# mixer-board4.net
KiCad netlist of a schematic drawn in EAGLE
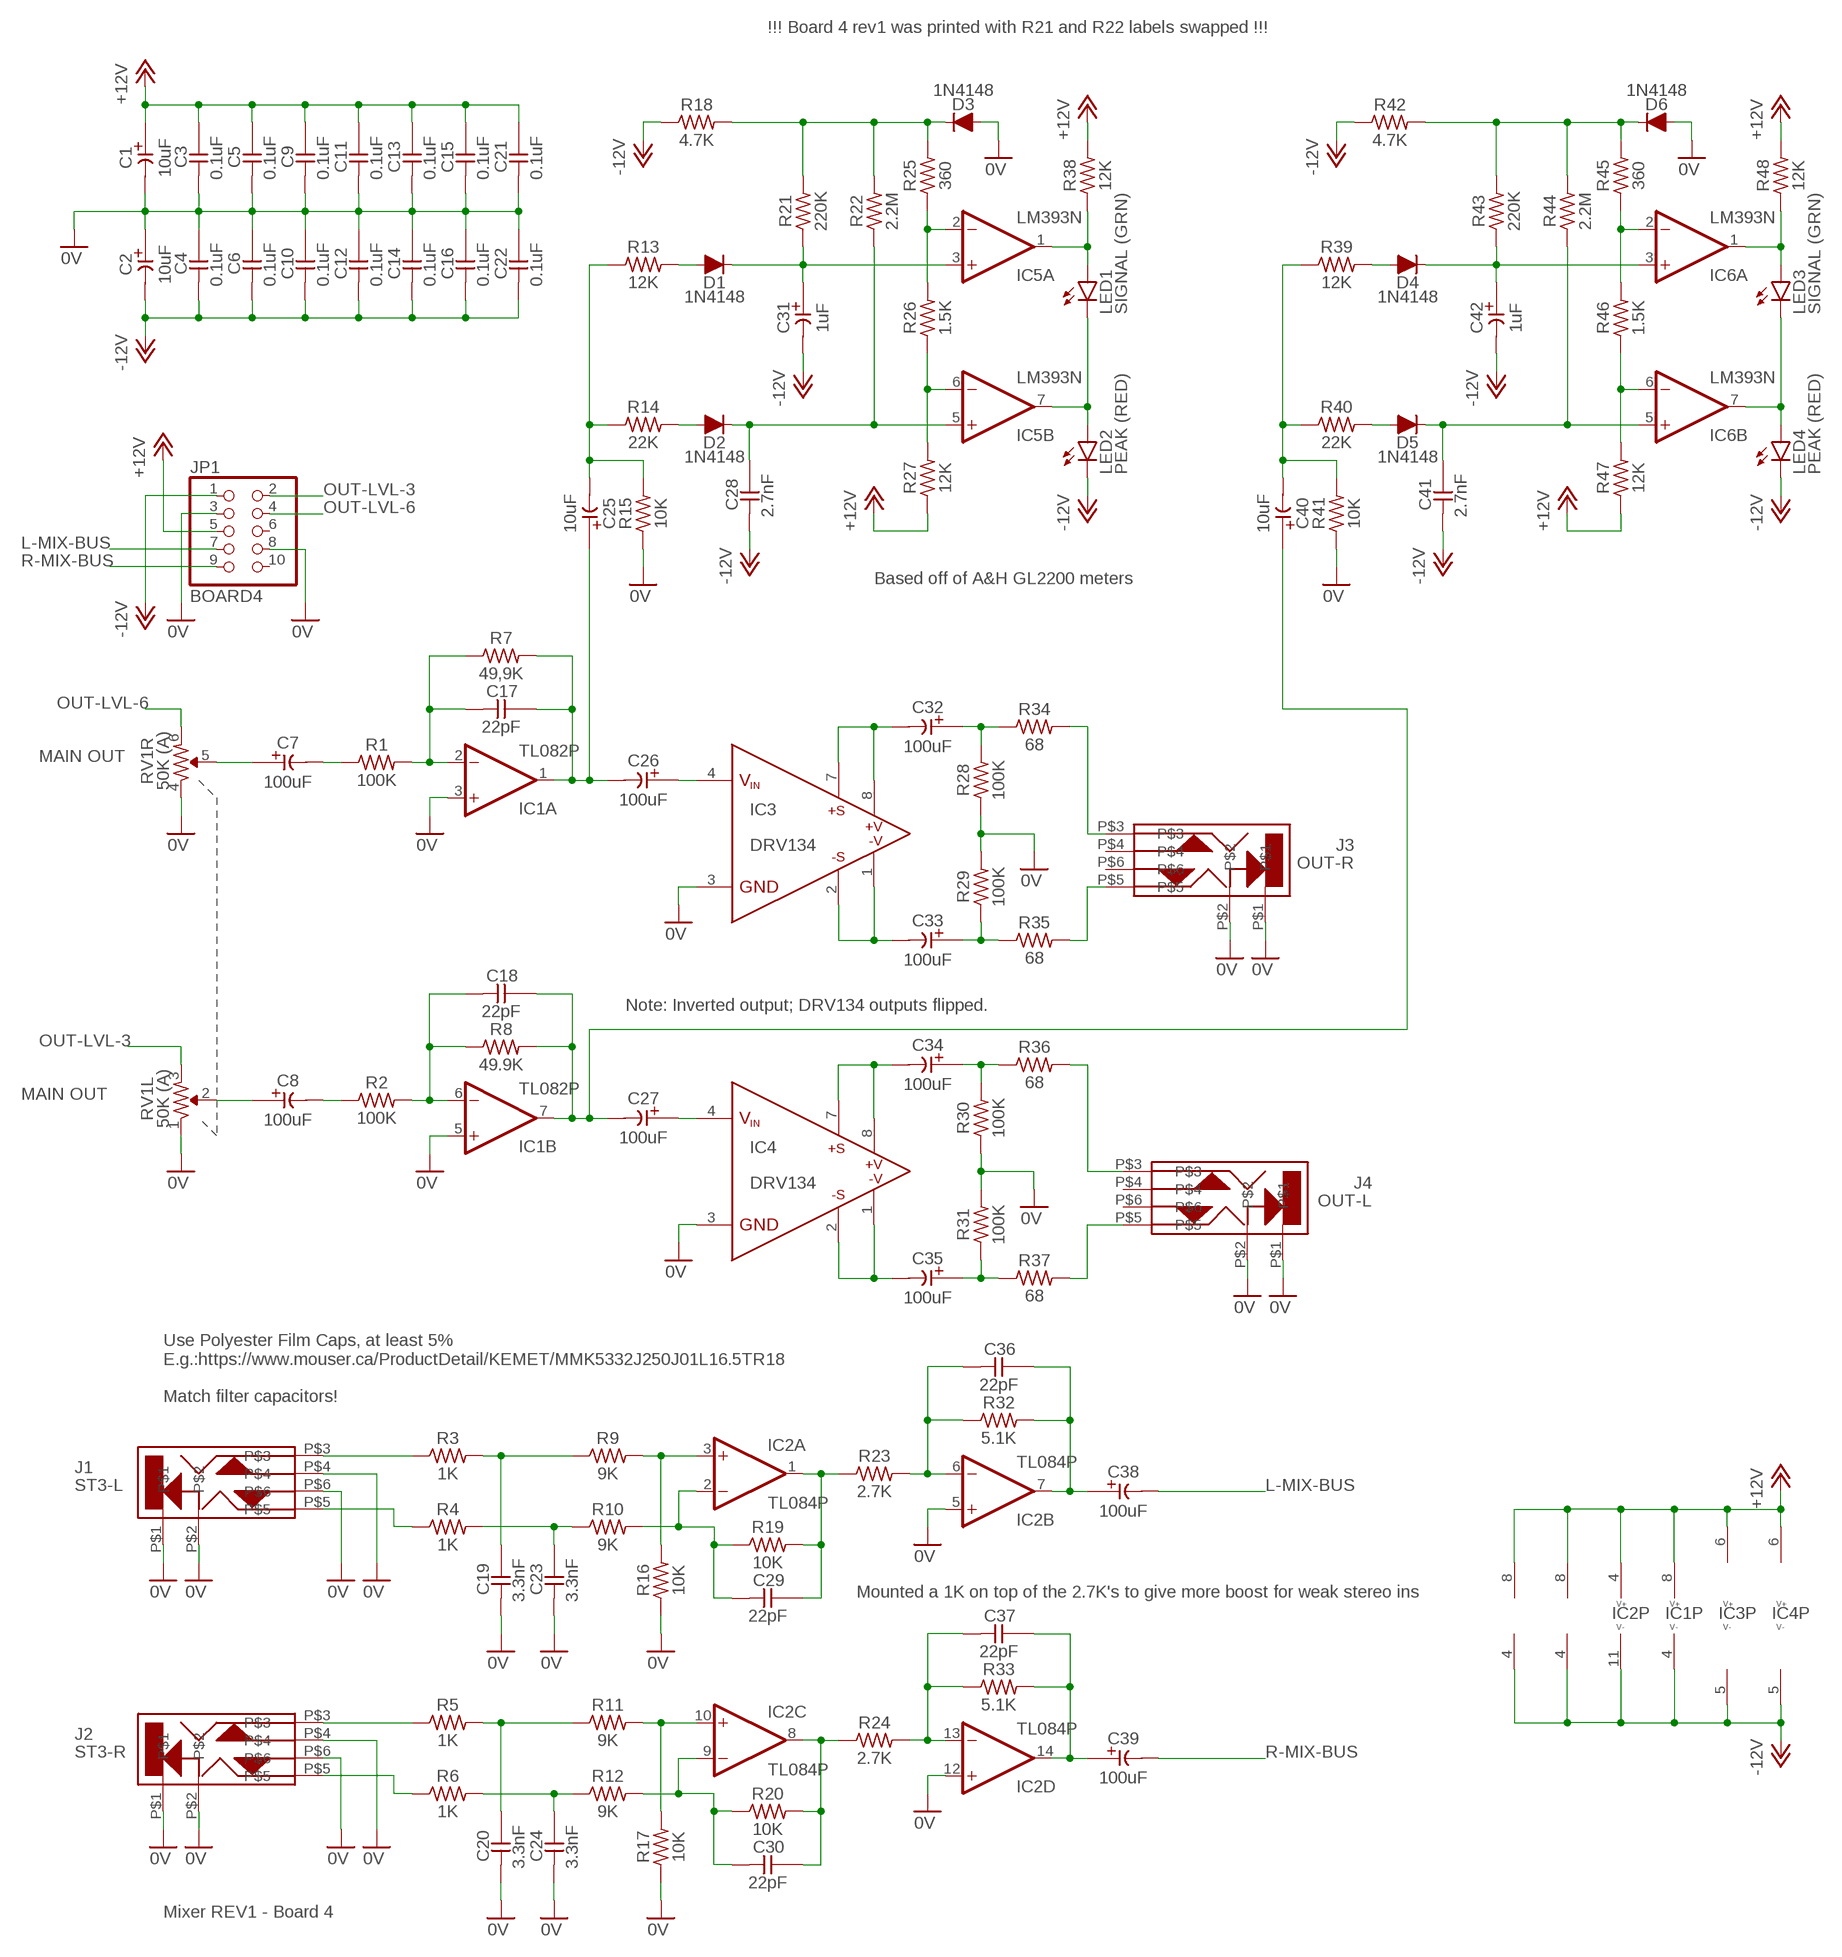
[diagram p0: schematic, sheet 1]

(export (version "E")
  (design (tool "Eeschema 10.0.6"))
  (components
    (comp (ref "C1")
      (value "10uF")
      (footprint "eagle-import:E2-5")
      (libsource (lib "eagle-import") (part "CE-USE2-5"))
    )
    (comp (ref "C2")
      (value "10uF")
      (footprint "eagle-import:E2-5")
      (libsource (lib "eagle-import") (part "CE-USE2-5"))
    )
    (comp (ref "C3")
      (value "0.1uF")
      (footprint "eagle-import:C025-024X044")
      (libsource (lib "eagle-import") (part "CC-US025-024X044"))
    )
    (comp (ref "C4")
      (value "0.1uF")
      (footprint "eagle-import:C025-024X044")
      (libsource (lib "eagle-import") (part "CC-US025-024X044"))
    )
    (comp (ref "C5")
      (value "0.1uF")
      (footprint "eagle-import:C025-024X044")
      (libsource (lib "eagle-import") (part "CC-US025-024X044"))
    )
    (comp (ref "C6")
      (value "0.1uF")
      (footprint "eagle-import:C025-024X044")
      (libsource (lib "eagle-import") (part "CC-US025-024X044"))
    )
    (comp (ref "C7")
      (value "100uF")
      (footprint "eagle-import:E5-8,5")
      (libsource (lib "eagle-import") (part "CE-USE5-8.5"))
    )
    (comp (ref "C8")
      (value "100uF")
      (footprint "eagle-import:E5-8,5")
      (libsource (lib "eagle-import") (part "CE-USE5-8.5"))
    )
    (comp (ref "C9")
      (value "0.1uF")
      (footprint "eagle-import:C025-024X044")
      (libsource (lib "eagle-import") (part "CC-US025-024X044"))
    )
    (comp (ref "C10")
      (value "0.1uF")
      (footprint "eagle-import:C025-024X044")
      (libsource (lib "eagle-import") (part "CC-US025-024X044"))
    )
    (comp (ref "C11")
      (value "0.1uF")
      (footprint "eagle-import:C025-024X044")
      (libsource (lib "eagle-import") (part "CC-US025-024X044"))
    )
    (comp (ref "C12")
      (value "0.1uF")
      (footprint "eagle-import:C025-024X044")
      (libsource (lib "eagle-import") (part "CC-US025-024X044"))
    )
    (comp (ref "C13")
      (value "0.1uF")
      (footprint "eagle-import:C025-024X044")
      (libsource (lib "eagle-import") (part "CC-US025-024X044"))
    )
    (comp (ref "C14")
      (value "0.1uF")
      (footprint "eagle-import:C025-024X044")
      (libsource (lib "eagle-import") (part "CC-US025-024X044"))
    )
    (comp (ref "C15")
      (value "0.1uF")
      (footprint "eagle-import:C025-024X044")
      (libsource (lib "eagle-import") (part "CC-US025-024X044"))
    )
    (comp (ref "C16")
      (value "0.1uF")
      (footprint "eagle-import:C025-024X044")
      (libsource (lib "eagle-import") (part "CC-US025-024X044"))
    )
    (comp (ref "C17")
      (value "22pF")
      (footprint "eagle-import:C025-024X044")
      (libsource (lib "eagle-import") (part "CC-US025-024X044"))
    )
    (comp (ref "C18")
      (value "22pF")
      (footprint "eagle-import:C025-024X044")
      (libsource (lib "eagle-import") (part "CC-US025-024X044"))
    )
    (comp (ref "C19")
      (value "3.3nF")
      (footprint "eagle-import:C050-024X044")
      (libsource (lib "eagle-import") (part "CC-US050-024X044"))
    )
    (comp (ref "C20")
      (value "3.3nF")
      (footprint "eagle-import:C050-024X044")
      (libsource (lib "eagle-import") (part "CC-US050-024X044"))
    )
    (comp (ref "C21")
      (value "0.1uF")
      (footprint "eagle-import:C025-024X044")
      (libsource (lib "eagle-import") (part "CC-US025-024X044"))
    )
    (comp (ref "C22")
      (value "0.1uF")
      (footprint "eagle-import:C025-024X044")
      (libsource (lib "eagle-import") (part "CC-US025-024X044"))
    )
    (comp (ref "C23")
      (value "3.3nF")
      (footprint "eagle-import:C050-024X044")
      (libsource (lib "eagle-import") (part "CC-US050-024X044"))
    )
    (comp (ref "C24")
      (value "3.3nF")
      (footprint "eagle-import:C050-024X044")
      (libsource (lib "eagle-import") (part "CC-US050-024X044"))
    )
    (comp (ref "C25")
      (value "10uF")
      (footprint "eagle-import:E2-5")
      (libsource (lib "eagle-import") (part "CE-USE2-5"))
    )
    (comp (ref "C26")
      (value "100uF")
      (footprint "eagle-import:E5-8,5")
      (libsource (lib "eagle-import") (part "CE-USE5-8.5"))
    )
    (comp (ref "C27")
      (value "100uF")
      (footprint "eagle-import:E5-8,5")
      (libsource (lib "eagle-import") (part "CE-USE5-8.5"))
    )
    (comp (ref "C28")
      (value "2.7nF")
      (footprint "eagle-import:C025-024X044")
      (libsource (lib "eagle-import") (part "CC-US025-024X044"))
    )
    (comp (ref "C29")
      (value "22pF")
      (footprint "eagle-import:C025-024X044")
      (libsource (lib "eagle-import") (part "CC-US025-024X044"))
    )
    (comp (ref "C30")
      (value "22pF")
      (footprint "eagle-import:C025-024X044")
      (libsource (lib "eagle-import") (part "CC-US025-024X044"))
    )
    (comp (ref "C31")
      (value "1uF")
      (footprint "eagle-import:E2-5")
      (libsource (lib "eagle-import") (part "CE-USE2-5"))
    )
    (comp (ref "C32")
      (value "100uF")
      (footprint "eagle-import:E5-8,5")
      (libsource (lib "eagle-import") (part "CE-USE5-8.5"))
    )
    (comp (ref "C33")
      (value "100uF")
      (footprint "eagle-import:E5-8,5")
      (libsource (lib "eagle-import") (part "CE-USE5-8.5"))
    )
    (comp (ref "C34")
      (value "100uF")
      (footprint "eagle-import:E5-8,5")
      (libsource (lib "eagle-import") (part "CE-USE5-8.5"))
    )
    (comp (ref "C35")
      (value "100uF")
      (footprint "eagle-import:E5-8,5")
      (libsource (lib "eagle-import") (part "CE-USE5-8.5"))
    )
    (comp (ref "C36")
      (value "22pF")
      (footprint "eagle-import:C025-024X044")
      (libsource (lib "eagle-import") (part "CC-US025-024X044"))
    )
    (comp (ref "C37")
      (value "22pF")
      (footprint "eagle-import:C025-024X044")
      (libsource (lib "eagle-import") (part "CC-US025-024X044"))
    )
    (comp (ref "C38")
      (value "100uF")
      (footprint "eagle-import:E5-8,5")
      (libsource (lib "eagle-import") (part "CE-USE5-8.5"))
    )
    (comp (ref "C39")
      (value "100uF")
      (footprint "eagle-import:E5-8,5")
      (libsource (lib "eagle-import") (part "CE-USE5-8.5"))
    )
    (comp (ref "C40")
      (value "10uF")
      (footprint "eagle-import:E2-5")
      (libsource (lib "eagle-import") (part "CE-USE2-5"))
    )
    (comp (ref "C41")
      (value "2.7nF")
      (footprint "eagle-import:C025-024X044")
      (libsource (lib "eagle-import") (part "CC-US025-024X044"))
    )
    (comp (ref "C42")
      (value "1uF")
      (footprint "eagle-import:E2-5")
      (libsource (lib "eagle-import") (part "CE-USE2-5"))
    )
    (comp (ref "D1")
      (value "1N4148")
      (footprint "eagle-import:DO34-5")
      (libsource (lib "eagle-import") (part "1N4148"))
    )
    (comp (ref "D2")
      (value "1N4148")
      (footprint "eagle-import:DO34-5")
      (libsource (lib "eagle-import") (part "1N4148"))
    )
    (comp (ref "D3")
      (value "1N4148")
      (footprint "eagle-import:DO34-5")
      (libsource (lib "eagle-import") (part "1N4148"))
    )
    (comp (ref "D4")
      (value "1N4148")
      (footprint "eagle-import:DO34-5")
      (libsource (lib "eagle-import") (part "1N4148"))
    )
    (comp (ref "D5")
      (value "1N4148")
      (footprint "eagle-import:DO34-5")
      (libsource (lib "eagle-import") (part "1N4148"))
    )
    (comp (ref "D6")
      (value "1N4148")
      (footprint "eagle-import:DO34-5")
      (libsource (lib "eagle-import") (part "1N4148"))
    )
    (comp (ref "IC1")
      (value "TL082P")
      (footprint "eagle-import:DIL08")
      (libsource (lib "eagle-import") (part "TL082P"))
    )
    (comp (ref "IC2")
      (value "TL084P")
      (footprint "eagle-import:DIL14")
      (libsource (lib "eagle-import") (part "TL084P"))
    )
    (comp (ref "IC3")
      (value "DRV134")
      (footprint "eagle-import:DIL08")
      (libsource (lib "eagle-import") (part "DRV134"))
    )
    (comp (ref "IC4")
      (value "DRV134")
      (footprint "eagle-import:DIL08")
      (libsource (lib "eagle-import") (part "DRV134"))
    )
    (comp (ref "IC5")
      (value "LM393N")
      (footprint "eagle-import:DIL08")
      (libsource (lib "eagle-import") (part "LM393N"))
    )
    (comp (ref "IC6")
      (value "LM393N")
      (footprint "eagle-import:DIL08")
      (libsource (lib "eagle-import") (part "LM393N"))
    )
    (comp (ref "J1")
      (value "ST3-L")
      (footprint "eagle-import:NYS216-U")
      (libsource (lib "eagle-import") (part "NYS216-U"))
    )
    (comp (ref "J2")
      (value "ST3-R")
      (footprint "eagle-import:NYS216-U")
      (libsource (lib "eagle-import") (part "NYS216-U"))
    )
    (comp (ref "J3")
      (value "OUT-R")
      (footprint "eagle-import:NYS216-U")
      (libsource (lib "eagle-import") (part "NYS216-U"))
    )
    (comp (ref "J4")
      (value "OUT-L")
      (footprint "eagle-import:NYS216-U")
      (libsource (lib "eagle-import") (part "NYS216-U"))
    )
    (comp (ref "JP1")
      (value "BOARD4")
      (footprint "eagle-import:2X05")
      (libsource (lib "eagle-import") (part "PINHD-2X5"))
    )
    (comp (ref "LED1")
      (value "SIGNAL (GRN)")
      (footprint "eagle-import:LED3MM")
      (libsource (lib "eagle-import") (part "LED3MM"))
    )
    (comp (ref "LED2")
      (value "PEAK (RED)")
      (footprint "eagle-import:LED3MM")
      (libsource (lib "eagle-import") (part "LED3MM"))
    )
    (comp (ref "LED3")
      (value "SIGNAL (GRN)")
      (footprint "eagle-import:LED3MM")
      (libsource (lib "eagle-import") (part "LED3MM"))
    )
    (comp (ref "LED4")
      (value "PEAK (RED)")
      (footprint "eagle-import:LED3MM")
      (libsource (lib "eagle-import") (part "LED3MM"))
    )
    (comp (ref "R1")
      (value "100K")
      (footprint "eagle-import:0207_7")
      (libsource (lib "eagle-import") (part "R"))
    )
    (comp (ref "R2")
      (value "100K")
      (footprint "eagle-import:0207_7")
      (libsource (lib "eagle-import") (part "R"))
    )
    (comp (ref "R3")
      (value "1K")
      (footprint "eagle-import:0207_7")
      (libsource (lib "eagle-import") (part "R"))
    )
    (comp (ref "R4")
      (value "1K")
      (footprint "eagle-import:0207_7")
      (libsource (lib "eagle-import") (part "R"))
    )
    (comp (ref "R5")
      (value "1K")
      (footprint "eagle-import:0207_7")
      (libsource (lib "eagle-import") (part "R"))
    )
    (comp (ref "R6")
      (value "1K")
      (footprint "eagle-import:0207_7")
      (libsource (lib "eagle-import") (part "R"))
    )
    (comp (ref "R7")
      (value "49,9K")
      (footprint "eagle-import:0207_7")
      (libsource (lib "eagle-import") (part "R"))
    )
    (comp (ref "R8")
      (value "49.9K")
      (footprint "eagle-import:0207_7")
      (libsource (lib "eagle-import") (part "R"))
    )
    (comp (ref "R9")
      (value "9K")
      (footprint "eagle-import:0207_7")
      (libsource (lib "eagle-import") (part "R"))
    )
    (comp (ref "R10")
      (value "9K")
      (footprint "eagle-import:0207_7")
      (libsource (lib "eagle-import") (part "R"))
    )
    (comp (ref "R11")
      (value "9K")
      (footprint "eagle-import:0207_7")
      (libsource (lib "eagle-import") (part "R"))
    )
    (comp (ref "R12")
      (value "9K")
      (footprint "eagle-import:0207_7")
      (libsource (lib "eagle-import") (part "R"))
    )
    (comp (ref "R13")
      (value "12K")
      (footprint "eagle-import:0207_7")
      (libsource (lib "eagle-import") (part "R"))
    )
    (comp (ref "R14")
      (value "22K")
      (footprint "eagle-import:0207_7")
      (libsource (lib "eagle-import") (part "R"))
    )
    (comp (ref "R15")
      (value "10K")
      (footprint "eagle-import:0207_7")
      (libsource (lib "eagle-import") (part "R"))
    )
    (comp (ref "R16")
      (value "10K")
      (footprint "eagle-import:0207_7")
      (libsource (lib "eagle-import") (part "R"))
    )
    (comp (ref "R17")
      (value "10K")
      (footprint "eagle-import:0207_7")
      (libsource (lib "eagle-import") (part "R"))
    )
    (comp (ref "R18")
      (value "4.7K")
      (footprint "eagle-import:0207_7")
      (libsource (lib "eagle-import") (part "R"))
    )
    (comp (ref "R19")
      (value "10K")
      (footprint "eagle-import:0207_7")
      (libsource (lib "eagle-import") (part "R"))
    )
    (comp (ref "R20")
      (value "10K")
      (footprint "eagle-import:0207_7")
      (libsource (lib "eagle-import") (part "R"))
    )
    (comp (ref "R21")
      (value "220K")
      (footprint "eagle-import:0207_7")
      (libsource (lib "eagle-import") (part "R"))
    )
    (comp (ref "R22")
      (value "2.2M")
      (footprint "eagle-import:0207_7")
      (libsource (lib "eagle-import") (part "R"))
    )
    (comp (ref "R23")
      (value "2.7K")
      (footprint "eagle-import:0207_7")
      (libsource (lib "eagle-import") (part "R"))
    )
    (comp (ref "R24")
      (value "2.7K")
      (footprint "eagle-import:0207_7")
      (libsource (lib "eagle-import") (part "R"))
    )
    (comp (ref "R25")
      (value "360")
      (footprint "eagle-import:0207_7")
      (libsource (lib "eagle-import") (part "R"))
    )
    (comp (ref "R26")
      (value "1.5K")
      (footprint "eagle-import:0207_7")
      (libsource (lib "eagle-import") (part "R"))
    )
    (comp (ref "R27")
      (value "12K")
      (footprint "eagle-import:0207_7")
      (libsource (lib "eagle-import") (part "R"))
    )
    (comp (ref "R28")
      (value "100K")
      (footprint "eagle-import:0207_7")
      (libsource (lib "eagle-import") (part "R"))
    )
    (comp (ref "R29")
      (value "100K")
      (footprint "eagle-import:0207_7")
      (libsource (lib "eagle-import") (part "R"))
    )
    (comp (ref "R30")
      (value "100K")
      (footprint "eagle-import:0207_7")
      (libsource (lib "eagle-import") (part "R"))
    )
    (comp (ref "R31")
      (value "100K")
      (footprint "eagle-import:0207_7")
      (libsource (lib "eagle-import") (part "R"))
    )
    (comp (ref "R32")
      (value "5.1K")
      (footprint "eagle-import:0207_7")
      (libsource (lib "eagle-import") (part "R"))
    )
    (comp (ref "R33")
      (value "5.1K")
      (footprint "eagle-import:0207_7")
      (libsource (lib "eagle-import") (part "R"))
    )
    (comp (ref "R34")
      (value "68")
      (footprint "eagle-import:0207_7")
      (libsource (lib "eagle-import") (part "R"))
    )
    (comp (ref "R35")
      (value "68")
      (footprint "eagle-import:0207_7")
      (libsource (lib "eagle-import") (part "R"))
    )
    (comp (ref "R36")
      (value "68")
      (footprint "eagle-import:0207_7")
      (libsource (lib "eagle-import") (part "R"))
    )
    (comp (ref "R37")
      (value "68")
      (footprint "eagle-import:0207_7")
      (libsource (lib "eagle-import") (part "R"))
    )
    (comp (ref "R38")
      (value "12K")
      (footprint "eagle-import:0207_7")
      (libsource (lib "eagle-import") (part "R"))
    )
    (comp (ref "R39")
      (value "12K")
      (footprint "eagle-import:0207_7")
      (libsource (lib "eagle-import") (part "R"))
    )
    (comp (ref "R40")
      (value "22K")
      (footprint "eagle-import:0207_7")
      (libsource (lib "eagle-import") (part "R"))
    )
    (comp (ref "R41")
      (value "10K")
      (footprint "eagle-import:0207_7")
      (libsource (lib "eagle-import") (part "R"))
    )
    (comp (ref "R42")
      (value "4.7K")
      (footprint "eagle-import:0207_7")
      (libsource (lib "eagle-import") (part "R"))
    )
    (comp (ref "R43")
      (value "220K")
      (footprint "eagle-import:0207_7")
      (libsource (lib "eagle-import") (part "R"))
    )
    (comp (ref "R44")
      (value "2.2M")
      (footprint "eagle-import:0207_7")
      (libsource (lib "eagle-import") (part "R"))
    )
    (comp (ref "R45")
      (value "360")
      (footprint "eagle-import:0207_7")
      (libsource (lib "eagle-import") (part "R"))
    )
    (comp (ref "R46")
      (value "1.5K")
      (footprint "eagle-import:0207_7")
      (libsource (lib "eagle-import") (part "R"))
    )
    (comp (ref "R47")
      (value "12K")
      (footprint "eagle-import:0207_7")
      (libsource (lib "eagle-import") (part "R"))
    )
    (comp (ref "R48")
      (value "12K")
      (footprint "eagle-import:0207_7")
      (libsource (lib "eagle-import") (part "R"))
    )
    (comp (ref "RV1")
      (value "50K (A)")
      (footprint "eagle-import:_COMMON_3RP_1610G")
      (libsource (lib "eagle-import") (part "R-VAR-ST"))
    )
  )
  (nets
    (net (code "1") (name "+12V") (class "Default")
      (node (ref "C1") (pin "+") (pinfunction "+_+") (pintype "passive"))
      (node (ref "C11") (pin "1") (pinfunction "1_1") (pintype "passive"))
      (node (ref "C13") (pin "1") (pinfunction "1_1") (pintype "passive"))
      (node (ref "C15") (pin "1") (pinfunction "1_1") (pintype "passive"))
      (node (ref "C21") (pin "1") (pinfunction "1_1") (pintype "passive"))
      (node (ref "C3") (pin "1") (pinfunction "1_1") (pintype "passive"))
      (node (ref "C5") (pin "1") (pinfunction "1_1") (pintype "passive"))
      (node (ref "C9") (pin "1") (pinfunction "1_1") (pintype "passive"))
      (node (ref "IC1") (pin "8") (pinfunction "V+_8") (pintype "power_in"))
      (node (ref "IC2") (pin "4") (pinfunction "V+_4") (pintype "power_in"))
      (node (ref "IC3") (pin "6") (pinfunction "V+_6") (pintype "power_in"))
      (node (ref "IC4") (pin "6") (pinfunction "V+_6") (pintype "power_in"))
      (node (ref "IC5") (pin "8") (pinfunction "V+_8") (pintype "power_in"))
      (node (ref "IC6") (pin "8") (pinfunction "V+_8") (pintype "power_in"))
      (node (ref "JP1") (pin "5") (pinfunction "5_5") (pintype "passive"))
      (node (ref "R27") (pin "1") (pinfunction "1_1") (pintype "passive"))
      (node (ref "R38") (pin "2") (pinfunction "2_2") (pintype "passive"))
      (node (ref "R47") (pin "1") (pinfunction "1_1") (pintype "passive"))
      (node (ref "R48") (pin "2") (pinfunction "2_2") (pintype "passive"))
    )
    (net (code "2") (name "-12V") (class "Default")
      (node (ref "C10") (pin "2") (pinfunction "2_2") (pintype "passive"))
      (node (ref "C12") (pin "2") (pinfunction "2_2") (pintype "passive"))
      (node (ref "C14") (pin "2") (pinfunction "2_2") (pintype "passive"))
      (node (ref "C16") (pin "2") (pinfunction "2_2") (pintype "passive"))
      (node (ref "C2") (pin "-") (pinfunction "-_-") (pintype "passive"))
      (node (ref "C22") (pin "2") (pinfunction "2_2") (pintype "passive"))
      (node (ref "C28") (pin "2") (pinfunction "2_2") (pintype "passive"))
      (node (ref "C31") (pin "-") (pinfunction "-_-") (pintype "passive"))
      (node (ref "C4") (pin "2") (pinfunction "2_2") (pintype "passive"))
      (node (ref "C41") (pin "2") (pinfunction "2_2") (pintype "passive"))
      (node (ref "C42") (pin "-") (pinfunction "-_-") (pintype "passive"))
      (node (ref "C6") (pin "2") (pinfunction "2_2") (pintype "passive"))
      (node (ref "IC1") (pin "4") (pinfunction "V-_4") (pintype "power_in"))
      (node (ref "IC2") (pin "11") (pinfunction "V-_11") (pintype "power_in"))
      (node (ref "IC3") (pin "5") (pinfunction "V-_5") (pintype "power_in"))
      (node (ref "IC4") (pin "5") (pinfunction "V-_5") (pintype "power_in"))
      (node (ref "IC5") (pin "4") (pinfunction "V-_4") (pintype "power_in"))
      (node (ref "IC6") (pin "4") (pinfunction "V-_4") (pintype "power_in"))
      (node (ref "JP1") (pin "1") (pinfunction "1_1") (pintype "passive"))
      (node (ref "LED2") (pin "K") (pinfunction "C_K") (pintype "passive"))
      (node (ref "LED4") (pin "K") (pinfunction "C_K") (pintype "passive"))
      (node (ref "R18") (pin "1") (pinfunction "1_1") (pintype "passive"))
      (node (ref "R42") (pin "1") (pinfunction "1_1") (pintype "passive"))
    )
    (net (code "3") (name "/L-MIX-BUS") (class "Default")
      (node (ref "C38") (pin "-") (pinfunction "-_-") (pintype "passive"))
      (node (ref "JP1") (pin "7") (pinfunction "7_7") (pintype "passive"))
    )
    (net (code "4") (name "/OUT-LVL-3") (class "Default")
      (node (ref "JP1") (pin "2") (pinfunction "2_2") (pintype "passive"))
      (node (ref "RV1") (pin "3") (pinfunction "3_3") (pintype "passive"))
    )
    (net (code "5") (name "/OUT-LVL-6") (class "Default")
      (node (ref "JP1") (pin "4") (pinfunction "4_4") (pintype "passive"))
      (node (ref "RV1") (pin "6") (pinfunction "3_6") (pintype "passive"))
    )
    (net (code "6") (name "/R-MIX-BUS") (class "Default")
      (node (ref "C39") (pin "-") (pinfunction "-_-") (pintype "passive"))
      (node (ref "JP1") (pin "9") (pinfunction "9_9") (pintype "passive"))
    )
    (net (code "7") (name "0V") (class "Default")
      (node (ref "C1") (pin "-") (pinfunction "-_-") (pintype "passive"))
      (node (ref "C10") (pin "1") (pinfunction "1_1") (pintype "passive"))
      (node (ref "C11") (pin "2") (pinfunction "2_2") (pintype "passive"))
      (node (ref "C12") (pin "1") (pinfunction "1_1") (pintype "passive"))
      (node (ref "C13") (pin "2") (pinfunction "2_2") (pintype "passive"))
      (node (ref "C14") (pin "1") (pinfunction "1_1") (pintype "passive"))
      (node (ref "C15") (pin "2") (pinfunction "2_2") (pintype "passive"))
      (node (ref "C16") (pin "1") (pinfunction "1_1") (pintype "passive"))
      (node (ref "C19") (pin "2") (pinfunction "2_2") (pintype "passive"))
      (node (ref "C2") (pin "+") (pinfunction "+_+") (pintype "passive"))
      (node (ref "C20") (pin "2") (pinfunction "2_2") (pintype "passive"))
      (node (ref "C21") (pin "2") (pinfunction "2_2") (pintype "passive"))
      (node (ref "C22") (pin "1") (pinfunction "1_1") (pintype "passive"))
      (node (ref "C23") (pin "2") (pinfunction "2_2") (pintype "passive"))
      (node (ref "C24") (pin "2") (pinfunction "2_2") (pintype "passive"))
      (node (ref "C3") (pin "2") (pinfunction "2_2") (pintype "passive"))
      (node (ref "C4") (pin "1") (pinfunction "1_1") (pintype "passive"))
      (node (ref "C5") (pin "2") (pinfunction "2_2") (pintype "passive"))
      (node (ref "C6") (pin "1") (pinfunction "1_1") (pintype "passive"))
      (node (ref "C9") (pin "2") (pinfunction "2_2") (pintype "passive"))
      (node (ref "D3") (pin "A") (pinfunction "A_A") (pintype "passive"))
      (node (ref "D6") (pin "A") (pinfunction "A_A") (pintype "passive"))
      (node (ref "IC1") (pin "3") (pinfunction "+IN_3") (pintype "input"))
      (node (ref "IC1") (pin "5") (pinfunction "+IN_5") (pintype "input"))
      (node (ref "IC2") (pin "12") (pinfunction "+IN_12") (pintype "input"))
      (node (ref "IC2") (pin "5") (pinfunction "+IN_5") (pintype "input"))
      (node (ref "IC3") (pin "3") (pinfunction "GND_3") (pintype "bidirectional"))
      (node (ref "IC4") (pin "3") (pinfunction "GND_3") (pintype "bidirectional"))
      (node (ref "J1") (pin "P$1") (pinfunction "P$1_P$1") (pintype "bidirectional"))
      (node (ref "J1") (pin "P$2") (pinfunction "P$2_P$2") (pintype "bidirectional"))
      (node (ref "J1") (pin "P$4") (pinfunction "P$4_P$4") (pintype "bidirectional"))
      (node (ref "J1") (pin "P$6") (pinfunction "P$6_P$6") (pintype "bidirectional"))
      (node (ref "J2") (pin "P$1") (pinfunction "P$1_P$1") (pintype "bidirectional"))
      (node (ref "J2") (pin "P$2") (pinfunction "P$2_P$2") (pintype "bidirectional"))
      (node (ref "J2") (pin "P$4") (pinfunction "P$4_P$4") (pintype "bidirectional"))
      (node (ref "J2") (pin "P$6") (pinfunction "P$6_P$6") (pintype "bidirectional"))
      (node (ref "J3") (pin "P$1") (pinfunction "P$1_P$1") (pintype "bidirectional"))
      (node (ref "J3") (pin "P$2") (pinfunction "P$2_P$2") (pintype "bidirectional"))
      (node (ref "J4") (pin "P$1") (pinfunction "P$1_P$1") (pintype "bidirectional"))
      (node (ref "J4") (pin "P$2") (pinfunction "P$2_P$2") (pintype "bidirectional"))
      (node (ref "JP1") (pin "3") (pinfunction "3_3") (pintype "passive"))
      (node (ref "JP1") (pin "8") (pinfunction "8_8") (pintype "passive"))
      (node (ref "R15") (pin "1") (pinfunction "1_1") (pintype "passive"))
      (node (ref "R16") (pin "1") (pinfunction "1_1") (pintype "passive"))
      (node (ref "R17") (pin "1") (pinfunction "1_1") (pintype "passive"))
      (node (ref "R28") (pin "1") (pinfunction "1_1") (pintype "passive"))
      (node (ref "R29") (pin "2") (pinfunction "2_2") (pintype "passive"))
      (node (ref "R30") (pin "1") (pinfunction "1_1") (pintype "passive"))
      (node (ref "R31") (pin "2") (pinfunction "2_2") (pintype "passive"))
      (node (ref "R41") (pin "1") (pinfunction "1_1") (pintype "passive"))
      (node (ref "RV1") (pin "1") (pinfunction "1_1") (pintype "passive"))
      (node (ref "RV1") (pin "4") (pinfunction "1_4") (pintype "passive"))
    )
    (net (code "8") (name "Net-(C7-Pad-)") (class "Default")
      (node (ref "C7") (pin "-") (pinfunction "-_-") (pintype "passive"))
      (node (ref "R1") (pin "1") (pinfunction "1_1") (pintype "passive"))
    )
    (net (code "9") (name "Net-(C8-Pad+)") (class "Default")
      (node (ref "C8") (pin "+") (pinfunction "+_+") (pintype "passive"))
      (node (ref "RV1") (pin "2") (pinfunction "2_2") (pintype "passive"))
    )
    (net (code "10") (name "Net-(C8-Pad-)") (class "Default")
      (node (ref "C8") (pin "-") (pinfunction "-_-") (pintype "passive"))
      (node (ref "R2") (pin "1") (pinfunction "1_1") (pintype "passive"))
    )
    (net (code "11") (name "Net-(C19-Pad1)") (class "Default")
      (node (ref "C19") (pin "1") (pinfunction "1_1") (pintype "passive"))
      (node (ref "R3") (pin "2") (pinfunction "2_2") (pintype "passive"))
      (node (ref "R9") (pin "1") (pinfunction "1_1") (pintype "passive"))
    )
    (net (code "12") (name "Net-(C20-Pad1)") (class "Default")
      (node (ref "C20") (pin "1") (pinfunction "1_1") (pintype "passive"))
      (node (ref "R11") (pin "1") (pinfunction "1_1") (pintype "passive"))
      (node (ref "R5") (pin "2") (pinfunction "2_2") (pintype "passive"))
    )
    (net (code "13") (name "Net-(C23-Pad1)") (class "Default")
      (node (ref "C23") (pin "1") (pinfunction "1_1") (pintype "passive"))
      (node (ref "R10") (pin "1") (pinfunction "1_1") (pintype "passive"))
      (node (ref "R4") (pin "2") (pinfunction "2_2") (pintype "passive"))
    )
    (net (code "14") (name "Net-(C24-Pad1)") (class "Default")
      (node (ref "C24") (pin "1") (pinfunction "1_1") (pintype "passive"))
      (node (ref "R12") (pin "1") (pinfunction "1_1") (pintype "passive"))
      (node (ref "R6") (pin "2") (pinfunction "2_2") (pintype "passive"))
    )
    (net (code "15") (name "Net-(C25-Pad-)") (class "Default")
      (node (ref "C25") (pin "-") (pinfunction "-_-") (pintype "passive"))
      (node (ref "R13") (pin "1") (pinfunction "1_1") (pintype "passive"))
      (node (ref "R14") (pin "1") (pinfunction "1_1") (pintype "passive"))
      (node (ref "R15") (pin "2") (pinfunction "2_2") (pintype "passive"))
    )
    (net (code "16") (name "Net-(C32-Pad+)") (class "Default")
      (node (ref "C32") (pin "+") (pinfunction "+_+") (pintype "passive"))
      (node (ref "R28") (pin "2") (pinfunction "2_2") (pintype "passive"))
      (node (ref "R34") (pin "1") (pinfunction "1_1") (pintype "passive"))
    )
    (net (code "17") (name "Net-(C33-Pad+)") (class "Default")
      (node (ref "C33") (pin "+") (pinfunction "+_+") (pintype "passive"))
      (node (ref "R29") (pin "1") (pinfunction "1_1") (pintype "passive"))
      (node (ref "R35") (pin "1") (pinfunction "1_1") (pintype "passive"))
    )
    (net (code "18") (name "Net-(C34-Pad+)") (class "Default")
      (node (ref "C34") (pin "+") (pinfunction "+_+") (pintype "passive"))
      (node (ref "R30") (pin "2") (pinfunction "2_2") (pintype "passive"))
      (node (ref "R36") (pin "1") (pinfunction "1_1") (pintype "passive"))
    )
    (net (code "19") (name "Net-(C35-Pad+)") (class "Default")
      (node (ref "C35") (pin "+") (pinfunction "+_+") (pintype "passive"))
      (node (ref "R31") (pin "1") (pinfunction "1_1") (pintype "passive"))
      (node (ref "R37") (pin "1") (pinfunction "1_1") (pintype "passive"))
    )
    (net (code "20") (name "Net-(C40-Pad-)") (class "Default")
      (node (ref "C40") (pin "-") (pinfunction "-_-") (pintype "passive"))
      (node (ref "R39") (pin "1") (pinfunction "1_1") (pintype "passive"))
      (node (ref "R40") (pin "1") (pinfunction "1_1") (pintype "passive"))
      (node (ref "R41") (pin "2") (pinfunction "2_2") (pintype "passive"))
    )
    (net (code "21") (name "Net-(D1-PadA)") (class "Default")
      (node (ref "D1") (pin "A") (pinfunction "A_A") (pintype "passive"))
      (node (ref "R13") (pin "2") (pinfunction "2_2") (pintype "passive"))
    )
    (net (code "22") (name "Net-(D2-PadA)") (class "Default")
      (node (ref "D2") (pin "A") (pinfunction "A_A") (pintype "passive"))
      (node (ref "R14") (pin "2") (pinfunction "2_2") (pintype "passive"))
    )
    (net (code "23") (name "Net-(D3-PadC)") (class "Default")
      (node (ref "D3") (pin "C") (pinfunction "C_C") (pintype "passive"))
      (node (ref "R18") (pin "2") (pinfunction "2_2") (pintype "passive"))
      (node (ref "R21") (pin "2") (pinfunction "2_2") (pintype "passive"))
      (node (ref "R22") (pin "2") (pinfunction "2_2") (pintype "passive"))
      (node (ref "R25") (pin "2") (pinfunction "2_2") (pintype "passive"))
    )
    (net (code "24") (name "Net-(D4-PadA)") (class "Default")
      (node (ref "D4") (pin "A") (pinfunction "A_A") (pintype "passive"))
      (node (ref "R39") (pin "2") (pinfunction "2_2") (pintype "passive"))
    )
    (net (code "25") (name "Net-(D5-PadA)") (class "Default")
      (node (ref "D5") (pin "A") (pinfunction "A_A") (pintype "passive"))
      (node (ref "R40") (pin "2") (pinfunction "2_2") (pintype "passive"))
    )
    (net (code "26") (name "Net-(D6-PadC)") (class "Default")
      (node (ref "D6") (pin "C") (pinfunction "C_C") (pintype "passive"))
      (node (ref "R42") (pin "2") (pinfunction "2_2") (pintype "passive"))
      (node (ref "R43") (pin "2") (pinfunction "2_2") (pintype "passive"))
      (node (ref "R44") (pin "2") (pinfunction "2_2") (pintype "passive"))
      (node (ref "R45") (pin "2") (pinfunction "2_2") (pintype "passive"))
    )
    (net (code "27") (name "Net-(IC1A--IN)") (class "Default")
      (node (ref "C17") (pin "2") (pinfunction "2_2") (pintype "passive"))
      (node (ref "IC1") (pin "2") (pinfunction "-IN_2") (pintype "input"))
      (node (ref "R1") (pin "2") (pinfunction "2_2") (pintype "passive"))
      (node (ref "R7") (pin "1") (pinfunction "1_1") (pintype "passive"))
    )
    (net (code "28") (name "Net-(IC1A-OUT)") (class "Default")
      (node (ref "C17") (pin "1") (pinfunction "1_1") (pintype "passive"))
      (node (ref "C25") (pin "+") (pinfunction "+_+") (pintype "passive"))
      (node (ref "C26") (pin "-") (pinfunction "-_-") (pintype "passive"))
      (node (ref "IC1") (pin "1") (pinfunction "OUT_1") (pintype "output"))
      (node (ref "R7") (pin "2") (pinfunction "2_2") (pintype "passive"))
    )
    (net (code "29") (name "Net-(IC1B--IN)") (class "Default")
      (node (ref "C18") (pin "2") (pinfunction "2_2") (pintype "passive"))
      (node (ref "IC1") (pin "6") (pinfunction "-IN_6") (pintype "input"))
      (node (ref "R2") (pin "2") (pinfunction "2_2") (pintype "passive"))
      (node (ref "R8") (pin "1") (pinfunction "1_1") (pintype "passive"))
    )
    (net (code "30") (name "Net-(IC1B-OUT)") (class "Default")
      (node (ref "C18") (pin "1") (pinfunction "1_1") (pintype "passive"))
      (node (ref "C27") (pin "-") (pinfunction "-_-") (pintype "passive"))
      (node (ref "C40") (pin "+") (pinfunction "+_+") (pintype "passive"))
      (node (ref "IC1") (pin "7") (pinfunction "OUT_7") (pintype "output"))
      (node (ref "R8") (pin "2") (pinfunction "2_2") (pintype "passive"))
    )
    (net (code "31") (name "Net-(IC2A-+IN)") (class "Default")
      (node (ref "IC2") (pin "3") (pinfunction "+IN_3") (pintype "input"))
      (node (ref "R16") (pin "2") (pinfunction "2_2") (pintype "passive"))
      (node (ref "R9") (pin "2") (pinfunction "2_2") (pintype "passive"))
    )
    (net (code "32") (name "Net-(IC2A--IN)") (class "Default")
      (node (ref "C29") (pin "2") (pinfunction "2_2") (pintype "passive"))
      (node (ref "IC2") (pin "2") (pinfunction "-IN_2") (pintype "input"))
      (node (ref "R10") (pin "2") (pinfunction "2_2") (pintype "passive"))
      (node (ref "R19") (pin "1") (pinfunction "1_1") (pintype "passive"))
    )
    (net (code "33") (name "Net-(IC2A-OUT)") (class "Default")
      (node (ref "C29") (pin "1") (pinfunction "1_1") (pintype "passive"))
      (node (ref "IC2") (pin "1") (pinfunction "OUT_1") (pintype "output"))
      (node (ref "R19") (pin "2") (pinfunction "2_2") (pintype "passive"))
      (node (ref "R23") (pin "1") (pinfunction "1_1") (pintype "passive"))
    )
    (net (code "34") (name "Net-(IC2B--IN)") (class "Default")
      (node (ref "C36") (pin "2") (pinfunction "2_2") (pintype "passive"))
      (node (ref "IC2") (pin "6") (pinfunction "-IN_6") (pintype "input"))
      (node (ref "R23") (pin "2") (pinfunction "2_2") (pintype "passive"))
      (node (ref "R32") (pin "1") (pinfunction "1_1") (pintype "passive"))
    )
    (net (code "35") (name "Net-(IC2B-OUT)") (class "Default")
      (node (ref "C36") (pin "1") (pinfunction "1_1") (pintype "passive"))
      (node (ref "C38") (pin "+") (pinfunction "+_+") (pintype "passive"))
      (node (ref "IC2") (pin "7") (pinfunction "OUT_7") (pintype "output"))
      (node (ref "R32") (pin "2") (pinfunction "2_2") (pintype "passive"))
    )
    (net (code "36") (name "Net-(IC2C-+IN)") (class "Default")
      (node (ref "IC2") (pin "10") (pinfunction "+IN_10") (pintype "input"))
      (node (ref "R11") (pin "2") (pinfunction "2_2") (pintype "passive"))
      (node (ref "R17") (pin "2") (pinfunction "2_2") (pintype "passive"))
    )
    (net (code "37") (name "Net-(IC2C--IN)") (class "Default")
      (node (ref "C30") (pin "2") (pinfunction "2_2") (pintype "passive"))
      (node (ref "IC2") (pin "9") (pinfunction "-IN_9") (pintype "input"))
      (node (ref "R12") (pin "2") (pinfunction "2_2") (pintype "passive"))
      (node (ref "R20") (pin "1") (pinfunction "1_1") (pintype "passive"))
    )
    (net (code "38") (name "Net-(IC2C-OUT)") (class "Default")
      (node (ref "C30") (pin "1") (pinfunction "1_1") (pintype "passive"))
      (node (ref "IC2") (pin "8") (pinfunction "OUT_8") (pintype "output"))
      (node (ref "R20") (pin "2") (pinfunction "2_2") (pintype "passive"))
      (node (ref "R24") (pin "1") (pinfunction "1_1") (pintype "passive"))
    )
    (net (code "39") (name "Net-(IC2D--IN)") (class "Default")
      (node (ref "C37") (pin "2") (pinfunction "2_2") (pintype "passive"))
      (node (ref "IC2") (pin "13") (pinfunction "-IN_13") (pintype "input"))
      (node (ref "R24") (pin "2") (pinfunction "2_2") (pintype "passive"))
      (node (ref "R33") (pin "1") (pinfunction "1_1") (pintype "passive"))
    )
    (net (code "40") (name "Net-(IC2D-OUT)") (class "Default")
      (node (ref "C37") (pin "1") (pinfunction "1_1") (pintype "passive"))
      (node (ref "C39") (pin "+") (pinfunction "+_+") (pintype "passive"))
      (node (ref "IC2") (pin "14") (pinfunction "OUT_14") (pintype "output"))
      (node (ref "R33") (pin "2") (pinfunction "2_2") (pintype "passive"))
    )
    (net (code "41") (name "Net-(IC3A-+SENSE)") (class "Default")
      (node (ref "C32") (pin "-") (pinfunction "-_-") (pintype "passive"))
      (node (ref "IC3") (pin "7") (pinfunction "+SENSE_7") (pintype "bidirectional"))
      (node (ref "IC3") (pin "8") (pinfunction "+V0_8") (pintype "bidirectional"))
    )
    (net (code "42") (name "Net-(IC3A--SENSE)") (class "Default")
      (node (ref "C33") (pin "-") (pinfunction "-_-") (pintype "passive"))
      (node (ref "IC3") (pin "1") (pinfunction "-V0_1") (pintype "bidirectional"))
      (node (ref "IC3") (pin "2") (pinfunction "-SENSE_2") (pintype "bidirectional"))
    )
    (net (code "43") (name "Net-(IC3A-VIN)") (class "Default")
      (node (ref "C26") (pin "+") (pinfunction "+_+") (pintype "passive"))
      (node (ref "IC3") (pin "4") (pinfunction "VIN_4") (pintype "bidirectional"))
    )
    (net (code "44") (name "Net-(IC4A-+SENSE)") (class "Default")
      (node (ref "C34") (pin "-") (pinfunction "-_-") (pintype "passive"))
      (node (ref "IC4") (pin "7") (pinfunction "+SENSE_7") (pintype "bidirectional"))
      (node (ref "IC4") (pin "8") (pinfunction "+V0_8") (pintype "bidirectional"))
    )
    (net (code "45") (name "Net-(IC4A--SENSE)") (class "Default")
      (node (ref "C35") (pin "-") (pinfunction "-_-") (pintype "passive"))
      (node (ref "IC4") (pin "1") (pinfunction "-V0_1") (pintype "bidirectional"))
      (node (ref "IC4") (pin "2") (pinfunction "-SENSE_2") (pintype "bidirectional"))
    )
    (net (code "46") (name "Net-(IC4A-VIN)") (class "Default")
      (node (ref "C27") (pin "+") (pinfunction "+_+") (pintype "passive"))
      (node (ref "IC4") (pin "4") (pinfunction "VIN_4") (pintype "bidirectional"))
    )
    (net (code "47") (name "Net-(IC5A-+IN)") (class "Default")
      (node (ref "C31") (pin "+") (pinfunction "+_+") (pintype "passive"))
      (node (ref "D1") (pin "C") (pinfunction "C_C") (pintype "passive"))
      (node (ref "IC5") (pin "3") (pinfunction "+IN_3") (pintype "input"))
      (node (ref "R21") (pin "1") (pinfunction "1_1") (pintype "passive"))
    )
    (net (code "48") (name "Net-(IC5A--IN)") (class "Default")
      (node (ref "IC5") (pin "2") (pinfunction "-IN_2") (pintype "input"))
      (node (ref "R25") (pin "1") (pinfunction "1_1") (pintype "passive"))
      (node (ref "R26") (pin "2") (pinfunction "2_2") (pintype "passive"))
    )
    (net (code "49") (name "Net-(IC5A-OUT)") (class "Default")
      (node (ref "IC5") (pin "1") (pinfunction "OUT_1") (pintype "output"))
      (node (ref "LED1") (pin "A") (pinfunction "A_A") (pintype "passive"))
      (node (ref "R38") (pin "1") (pinfunction "1_1") (pintype "passive"))
    )
    (net (code "50") (name "Net-(IC5B-+IN)") (class "Default")
      (node (ref "C28") (pin "1") (pinfunction "1_1") (pintype "passive"))
      (node (ref "D2") (pin "C") (pinfunction "C_C") (pintype "passive"))
      (node (ref "IC5") (pin "5") (pinfunction "+IN_5") (pintype "input"))
      (node (ref "R22") (pin "1") (pinfunction "1_1") (pintype "passive"))
    )
    (net (code "51") (name "Net-(IC5B--IN)") (class "Default")
      (node (ref "IC5") (pin "6") (pinfunction "-IN_6") (pintype "input"))
      (node (ref "R26") (pin "1") (pinfunction "1_1") (pintype "passive"))
      (node (ref "R27") (pin "2") (pinfunction "2_2") (pintype "passive"))
    )
    (net (code "52") (name "Net-(IC5B-OUT)") (class "Default")
      (node (ref "IC5") (pin "7") (pinfunction "OUT_7") (pintype "output"))
      (node (ref "LED1") (pin "K") (pinfunction "C_K") (pintype "passive"))
      (node (ref "LED2") (pin "A") (pinfunction "A_A") (pintype "passive"))
    )
    (net (code "53") (name "Net-(IC6A-+IN)") (class "Default")
      (node (ref "C42") (pin "+") (pinfunction "+_+") (pintype "passive"))
      (node (ref "D4") (pin "C") (pinfunction "C_C") (pintype "passive"))
      (node (ref "IC6") (pin "3") (pinfunction "+IN_3") (pintype "input"))
      (node (ref "R43") (pin "1") (pinfunction "1_1") (pintype "passive"))
    )
    (net (code "54") (name "Net-(IC6A--IN)") (class "Default")
      (node (ref "IC6") (pin "2") (pinfunction "-IN_2") (pintype "input"))
      (node (ref "R45") (pin "1") (pinfunction "1_1") (pintype "passive"))
      (node (ref "R46") (pin "2") (pinfunction "2_2") (pintype "passive"))
    )
    (net (code "55") (name "Net-(IC6A-OUT)") (class "Default")
      (node (ref "IC6") (pin "1") (pinfunction "OUT_1") (pintype "output"))
      (node (ref "LED3") (pin "A") (pinfunction "A_A") (pintype "passive"))
      (node (ref "R48") (pin "1") (pinfunction "1_1") (pintype "passive"))
    )
    (net (code "56") (name "Net-(IC6B-+IN)") (class "Default")
      (node (ref "C41") (pin "1") (pinfunction "1_1") (pintype "passive"))
      (node (ref "D5") (pin "C") (pinfunction "C_C") (pintype "passive"))
      (node (ref "IC6") (pin "5") (pinfunction "+IN_5") (pintype "input"))
      (node (ref "R44") (pin "1") (pinfunction "1_1") (pintype "passive"))
    )
    (net (code "57") (name "Net-(IC6B--IN)") (class "Default")
      (node (ref "IC6") (pin "6") (pinfunction "-IN_6") (pintype "input"))
      (node (ref "R46") (pin "1") (pinfunction "1_1") (pintype "passive"))
      (node (ref "R47") (pin "2") (pinfunction "2_2") (pintype "passive"))
    )
    (net (code "58") (name "Net-(IC6B-OUT)") (class "Default")
      (node (ref "IC6") (pin "7") (pinfunction "OUT_7") (pintype "output"))
      (node (ref "LED3") (pin "K") (pinfunction "C_K") (pintype "passive"))
      (node (ref "LED4") (pin "A") (pinfunction "A_A") (pintype "passive"))
    )
    (net (code "59") (name "Net-(J1-PadP$3)") (class "Default")
      (node (ref "J1") (pin "P$3") (pinfunction "P$3_P$3") (pintype "bidirectional"))
      (node (ref "R3") (pin "1") (pinfunction "1_1") (pintype "passive"))
    )
    (net (code "60") (name "Net-(J1-PadP$5)") (class "Default")
      (node (ref "J1") (pin "P$5") (pinfunction "P$5_P$5") (pintype "bidirectional"))
      (node (ref "R4") (pin "1") (pinfunction "1_1") (pintype "passive"))
    )
    (net (code "61") (name "Net-(J2-PadP$3)") (class "Default")
      (node (ref "J2") (pin "P$3") (pinfunction "P$3_P$3") (pintype "bidirectional"))
      (node (ref "R5") (pin "1") (pinfunction "1_1") (pintype "passive"))
    )
    (net (code "62") (name "Net-(J2-PadP$5)") (class "Default")
      (node (ref "J2") (pin "P$5") (pinfunction "P$5_P$5") (pintype "bidirectional"))
      (node (ref "R6") (pin "1") (pinfunction "1_1") (pintype "passive"))
    )
    (net (code "63") (name "Net-(J3-PadP$3)") (class "Default")
      (node (ref "J3") (pin "P$3") (pinfunction "P$3_P$3") (pintype "bidirectional"))
      (node (ref "R34") (pin "2") (pinfunction "2_2") (pintype "passive"))
    )
    (net (code "64") (name "Net-(J3-PadP$5)") (class "Default")
      (node (ref "J3") (pin "P$5") (pinfunction "P$5_P$5") (pintype "bidirectional"))
      (node (ref "R35") (pin "2") (pinfunction "2_2") (pintype "passive"))
    )
    (net (code "65") (name "Net-(J4-PadP$3)") (class "Default")
      (node (ref "J4") (pin "P$3") (pinfunction "P$3_P$3") (pintype "bidirectional"))
      (node (ref "R36") (pin "2") (pinfunction "2_2") (pintype "passive"))
    )
    (net (code "66") (name "Net-(J4-PadP$5)") (class "Default")
      (node (ref "J4") (pin "P$5") (pinfunction "P$5_P$5") (pintype "bidirectional"))
      (node (ref "R37") (pin "2") (pinfunction "2_2") (pintype "passive"))
    )
    (net (code "67") (name "Net-(RV1B-2)") (class "Default")
      (node (ref "C7") (pin "+") (pinfunction "+_+") (pintype "passive"))
      (node (ref "RV1") (pin "5") (pinfunction "2_5") (pintype "passive"))
    )
    (net (code "68") (name "unconnected-(J3-PadP$4)") (class "Default")
      (node (ref "J3") (pin "P$4") (pinfunction "P$4_P$4") (pintype "bidirectional"))
    )
    (net (code "69") (name "unconnected-(J3-PadP$6)") (class "Default")
      (node (ref "J3") (pin "P$6") (pinfunction "P$6_P$6") (pintype "bidirectional"))
    )
    (net (code "70") (name "unconnected-(J4-PadP$4)") (class "Default")
      (node (ref "J4") (pin "P$4") (pinfunction "P$4_P$4") (pintype "bidirectional"))
    )
    (net (code "71") (name "unconnected-(J4-PadP$6)") (class "Default")
      (node (ref "J4") (pin "P$6") (pinfunction "P$6_P$6") (pintype "bidirectional"))
    )
    (net (code "72") (name "unconnected-(JP1-Pad6)") (class "Default")
      (node (ref "JP1") (pin "6") (pinfunction "6_6") (pintype "passive"))
    )
    (net (code "73") (name "unconnected-(JP1-Pad10)") (class "Default")
      (node (ref "JP1") (pin "10") (pinfunction "10_10") (pintype "passive"))
    )
  )
)
